# RFNODE.net
KiCad netlist of a schematic drawn in EAGLE
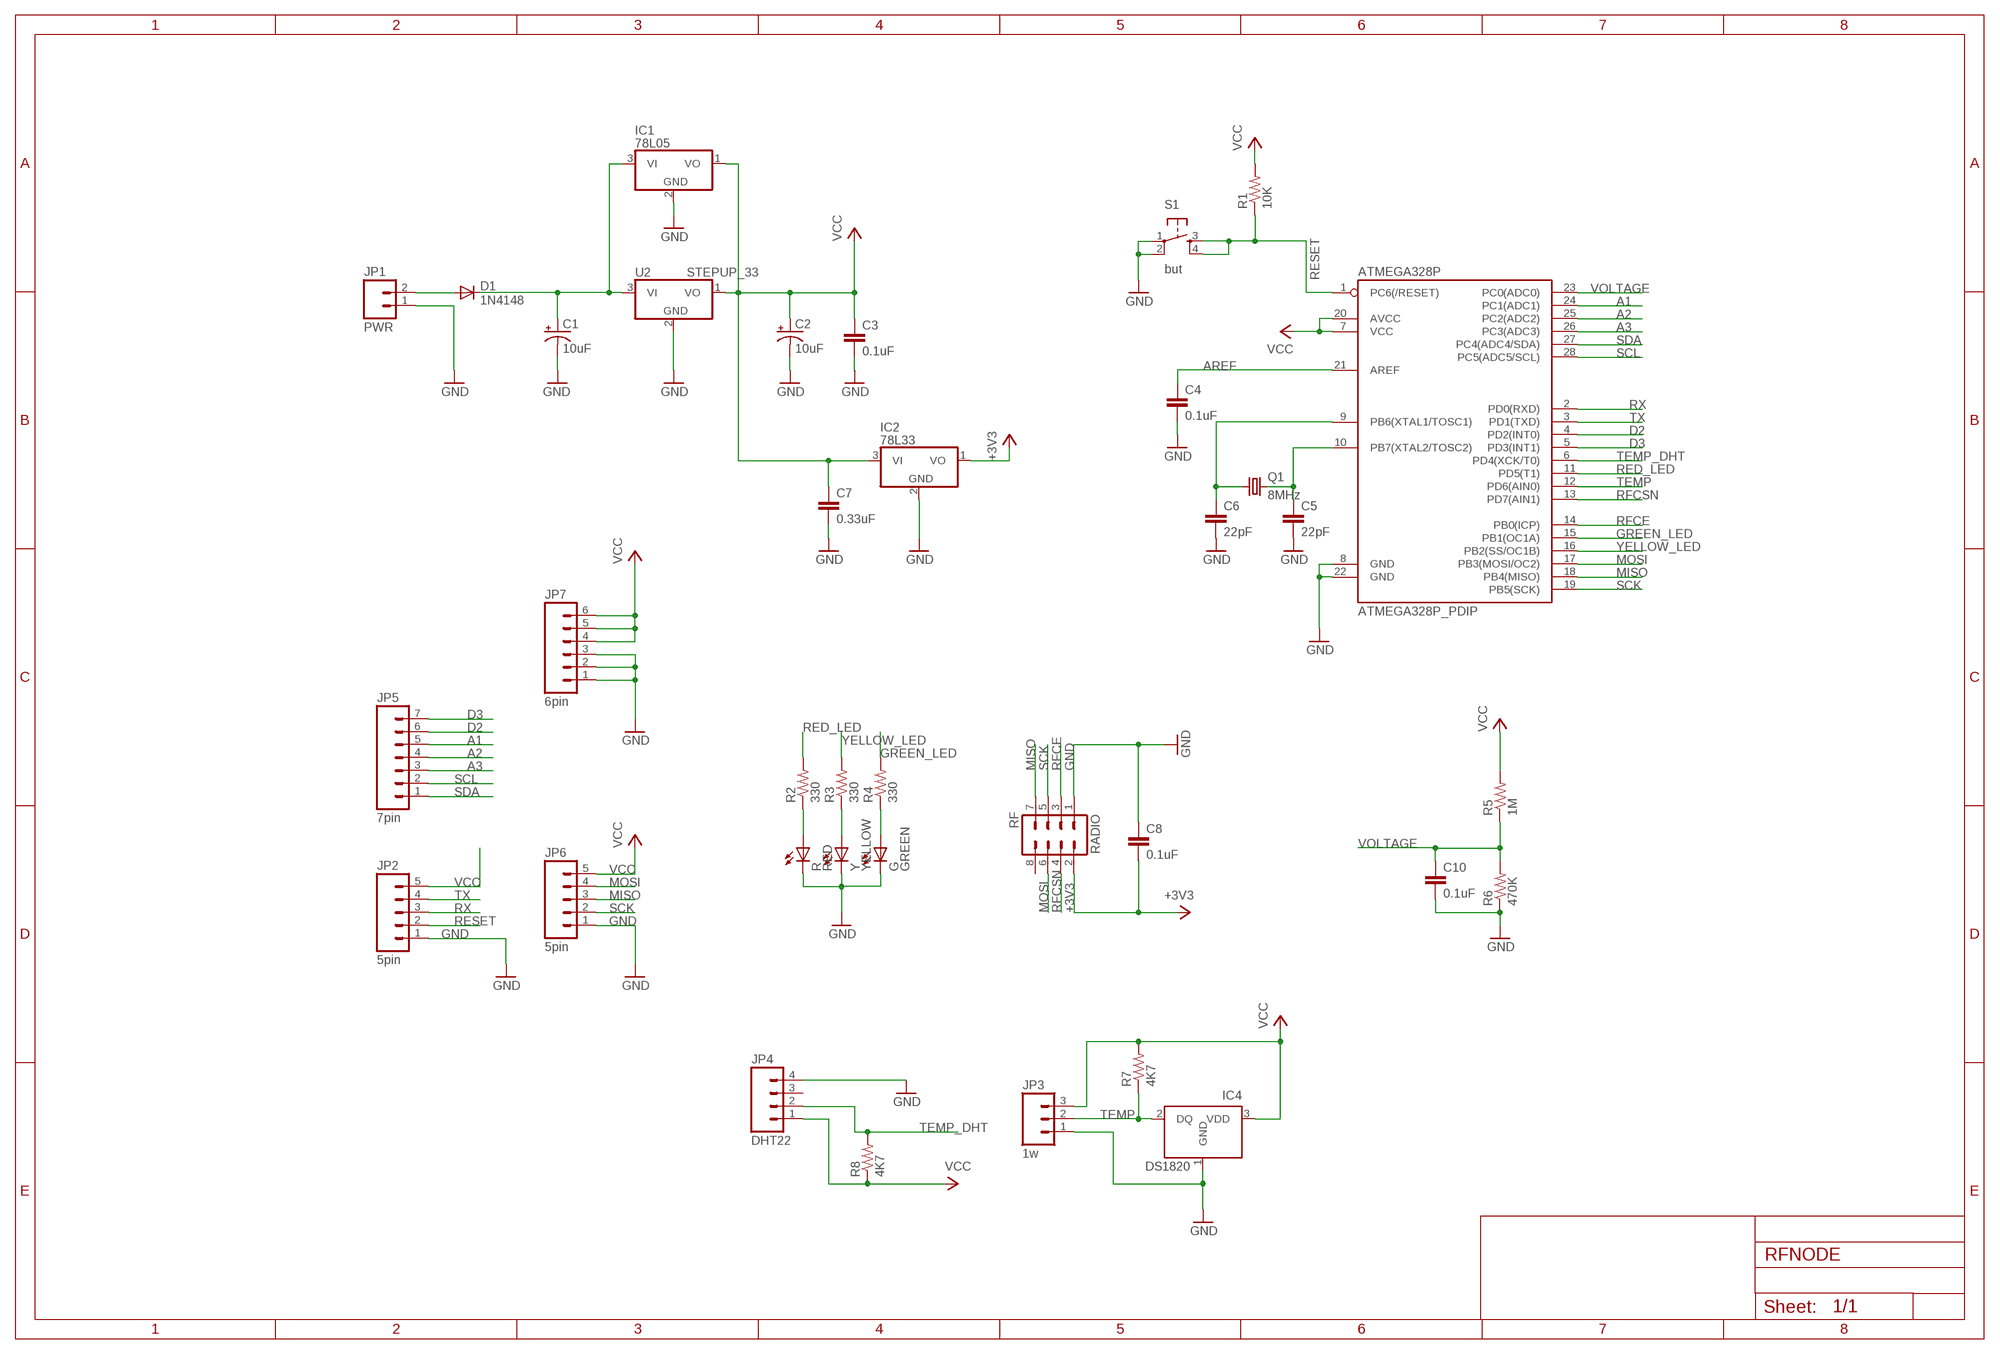
[diagram p0: schematic, sheet 1]

(export (version "E")
  (design (tool "Eeschema 10.0.6"))
  (components
    (comp (ref "ATMEGA328P")
      (value "ATMEGA328P_PDIP")
      (footprint "eagle-import:DIL28-3")
      (libsource (lib "eagle-import") (part "ATMEGA328P_PDIP"))
    )
    (comp (ref "C1")
      (value "10uF")
      (footprint "eagle-import:E2-4")
      (libsource (lib "eagle-import") (part "CPOL-USE2-4"))
    )
    (comp (ref "C2")
      (value "10uF")
      (footprint "eagle-import:E2-4")
      (libsource (lib "eagle-import") (part "CPOL-USE2-4"))
    )
    (comp (ref "C3")
      (value "0.1uF")
      (footprint "eagle-import:C1206")
      (libsource (lib "eagle-import") (part "C-EUC1206"))
    )
    (comp (ref "C4")
      (value "0.1uF")
      (footprint "eagle-import:C1206")
      (libsource (lib "eagle-import") (part "C-EUC1206"))
    )
    (comp (ref "C5")
      (value "22pF")
      (footprint "eagle-import:C1206")
      (libsource (lib "eagle-import") (part "C-EUC1206"))
    )
    (comp (ref "C6")
      (value "22pF")
      (footprint "eagle-import:C1206")
      (libsource (lib "eagle-import") (part "C-EUC1206"))
    )
    (comp (ref "C7")
      (value "0.33uF")
      (footprint "eagle-import:C1206")
      (libsource (lib "eagle-import") (part "C-EUC1206"))
    )
    (comp (ref "C8")
      (value "0.1uF")
      (footprint "eagle-import:C1206")
      (libsource (lib "eagle-import") (part "C-EUC1206"))
    )
    (comp (ref "C10")
      (value "0.1uF")
      (footprint "eagle-import:C1206")
      (libsource (lib "eagle-import") (part "C-EUC1206"))
    )
    (comp (ref "D1")
      (value "1N4148")
      (footprint "eagle-import:D-2.5")
      (libsource (lib "eagle-import") (part "DIODE-D-2.5"))
    )
    (comp (ref "G")
      (value "GREEN")
      (footprint "eagle-import:LED3MM")
      (libsource (lib "eagle-import") (part "LED3MM"))
    )
    (comp (ref "IC1")
      (value "78L05")
      (footprint "eagle-import:TO92")
      (libsource (lib "eagle-import") (part "78ZL05"))
    )
    (comp (ref "IC2")
      (value "78L33")
      (footprint "eagle-import:TO92")
      (libsource (lib "eagle-import") (part "78ZL05"))
    )
    (comp (ref "IC4")
      (value "DS1820")
      (footprint "eagle-import:TO-92")
      (libsource (lib "eagle-import") (part "DS1820"))
    )
    (comp (ref "JP1")
      (value "PWR")
      (footprint "eagle-import:MOLEX-1X2")
      (libsource (lib "eagle-import") (part "M02POLAR"))
    )
    (comp (ref "JP2")
      (value "5pin")
      (footprint "eagle-import:1X05")
      (libsource (lib "eagle-import") (part "M05PTH"))
    )
    (comp (ref "JP3")
      (value "1w")
      (footprint "eagle-import:1X03")
      (libsource (lib "eagle-import") (part "M03PTH"))
    )
    (comp (ref "JP4")
      (value "DHT22")
      (footprint "eagle-import:1X04")
      (libsource (lib "eagle-import") (part "M04PTH"))
    )
    (comp (ref "JP5")
      (value "7pin")
      (footprint "eagle-import:1X07")
      (libsource (lib "eagle-import") (part "M07"))
    )
    (comp (ref "JP6")
      (value "5pin")
      (footprint "eagle-import:1X05")
      (libsource (lib "eagle-import") (part "M05PTH"))
    )
    (comp (ref "JP7")
      (value "6pin")
      (footprint "eagle-import:1X06")
      (libsource (lib "eagle-import") (part "M06SIP"))
    )
    (comp (ref "Q1")
      (value "8MHz")
      (footprint "eagle-import:HC49_S")
      (libsource (lib "eagle-import") (part "CRYSTALHC49S"))
    )
    (comp (ref "R")
      (value "RED")
      (footprint "eagle-import:LED3MM")
      (libsource (lib "eagle-import") (part "LED3MM"))
    )
    (comp (ref "R1")
      (value "10K")
      (footprint "eagle-import:R1206")
      (libsource (lib "eagle-import") (part "R-US_R1206"))
    )
    (comp (ref "R2")
      (value "330")
      (footprint "eagle-import:R1206")
      (libsource (lib "eagle-import") (part "R-US_R1206"))
    )
    (comp (ref "R3")
      (value "330")
      (footprint "eagle-import:R1206")
      (libsource (lib "eagle-import") (part "R-US_R1206"))
    )
    (comp (ref "R4")
      (value "330")
      (footprint "eagle-import:R1206")
      (libsource (lib "eagle-import") (part "R-US_R1206"))
    )
    (comp (ref "R5")
      (value "1M")
      (footprint "eagle-import:R1206")
      (libsource (lib "eagle-import") (part "R-US_R1206"))
    )
    (comp (ref "R6")
      (value "470K")
      (footprint "eagle-import:R1206")
      (libsource (lib "eagle-import") (part "R-US_R1206"))
    )
    (comp (ref "R7")
      (value "4K7")
      (footprint "eagle-import:R1206")
      (libsource (lib "eagle-import") (part "R-US_R1206"))
    )
    (comp (ref "R8")
      (value "4K7")
      (footprint "eagle-import:R1206")
      (libsource (lib "eagle-import") (part "R-US_R1206"))
    )
    (comp (ref "RADIO")
      (value "RF")
      (footprint "eagle-import:2X4")
      (libsource (lib "eagle-import") (part "M04X2"))
    )
    (comp (ref "S1")
      (value "but")
      (footprint "eagle-import:TACTILE-PTH")
      (libsource (lib "eagle-import") (part "TAC_SWITCHPTH"))
    )
    (comp (ref "U2")
      (value "STEPUP_33")
      (footprint "eagle-import:1X03")
      (libsource (lib "eagle-import") (part "DC-DC_STEPUP"))
    )
    (comp (ref "Y")
      (value "YELLOW")
      (footprint "eagle-import:LED3MM")
      (libsource (lib "eagle-import") (part "LED3MM"))
    )
  )
  (nets
    (net (code "1") (name "+3V3") (class "Default")
      (node (ref "C8") (pin "2") (pinfunction "2_2") (pintype "passive"))
      (node (ref "IC2") (pin "1") (pinfunction "VO_1") (pintype "passive"))
      (node (ref "RADIO") (pin "2") (pinfunction "2_2") (pintype "passive"))
    )
    (net (code "2") (name "/A1") (class "Default")
      (node (ref "ATMEGA328P") (pin "24") (pinfunction "PC1(ADC1)_24") (pintype "bidirectional"))
      (node (ref "JP5") (pin "5") (pinfunction "5_5") (pintype "passive"))
    )
    (net (code "3") (name "/A2") (class "Default")
      (node (ref "ATMEGA328P") (pin "25") (pinfunction "PC2(ADC2)_25") (pintype "bidirectional"))
      (node (ref "JP5") (pin "4") (pinfunction "4_4") (pintype "passive"))
    )
    (net (code "4") (name "/A3") (class "Default")
      (node (ref "ATMEGA328P") (pin "26") (pinfunction "PC3(ADC3)_26") (pintype "bidirectional"))
      (node (ref "JP5") (pin "3") (pinfunction "3_3") (pintype "passive"))
    )
    (net (code "5") (name "/AREF") (class "Default")
      (node (ref "ATMEGA328P") (pin "21") (pinfunction "AREF_21") (pintype "bidirectional"))
      (node (ref "C4") (pin "1") (pinfunction "1_1") (pintype "passive"))
    )
    (net (code "6") (name "/D2") (class "Default")
      (node (ref "ATMEGA328P") (pin "4") (pinfunction "PD2(INT0)_4") (pintype "bidirectional"))
      (node (ref "JP5") (pin "6") (pinfunction "6_6") (pintype "passive"))
    )
    (net (code "7") (name "/D3") (class "Default")
      (node (ref "ATMEGA328P") (pin "5") (pinfunction "PD3(INT1)_5") (pintype "bidirectional"))
      (node (ref "JP5") (pin "7") (pinfunction "7_7") (pintype "passive"))
    )
    (net (code "8") (name "/GREEN_LED") (class "Default")
      (node (ref "ATMEGA328P") (pin "15") (pinfunction "PB1(OC1A)_15") (pintype "bidirectional"))
      (node (ref "R4") (pin "2") (pinfunction "2_2") (pintype "passive"))
    )
    (net (code "9") (name "/MISO") (class "Default")
      (node (ref "ATMEGA328P") (pin "18") (pinfunction "PB4(MISO)_18") (pintype "bidirectional"))
      (node (ref "JP6") (pin "4") (pinfunction "4_4") (pintype "passive"))
      (node (ref "RADIO") (pin "7") (pinfunction "7_7") (pintype "passive"))
    )
    (net (code "10") (name "/MOSI") (class "Default")
      (node (ref "ATMEGA328P") (pin "17") (pinfunction "PB3(MOSI/OC2)_17") (pintype "bidirectional"))
      (node (ref "JP6") (pin "3") (pinfunction "3_3") (pintype "passive"))
      (node (ref "RADIO") (pin "6") (pinfunction "6_6") (pintype "passive"))
    )
    (net (code "11") (name "/RED_LED") (class "Default")
      (node (ref "ATMEGA328P") (pin "11") (pinfunction "PD5(T1)_11") (pintype "bidirectional"))
      (node (ref "R2") (pin "2") (pinfunction "2_2") (pintype "passive"))
    )
    (net (code "12") (name "/RESET") (class "Default")
      (node (ref "ATMEGA328P") (pin "1") (pinfunction "PC6(/RESET)_1") (pintype "bidirectional"))
      (node (ref "JP2") (pin "2") (pinfunction "2_2") (pintype "passive"))
      (node (ref "R1") (pin "1") (pinfunction "1_1") (pintype "passive"))
      (node (ref "S1") (pin "3") (pinfunction "3_3") (pintype "passive"))
      (node (ref "S1") (pin "4") (pinfunction "4_4") (pintype "passive"))
    )
    (net (code "13") (name "/RFCE") (class "Default")
      (node (ref "ATMEGA328P") (pin "14") (pinfunction "PB0(ICP)_14") (pintype "bidirectional"))
      (node (ref "RADIO") (pin "3") (pinfunction "3_3") (pintype "passive"))
    )
    (net (code "14") (name "/RFCSN") (class "Default")
      (node (ref "ATMEGA328P") (pin "13") (pinfunction "PD7(AIN1)_13") (pintype "bidirectional"))
      (node (ref "RADIO") (pin "4") (pinfunction "4_4") (pintype "passive"))
    )
    (net (code "15") (name "/RX") (class "Default")
      (node (ref "ATMEGA328P") (pin "2") (pinfunction "PD0(RXD)_2") (pintype "bidirectional"))
      (node (ref "JP2") (pin "3") (pinfunction "3_3") (pintype "passive"))
    )
    (net (code "16") (name "/SCK") (class "Default")
      (node (ref "ATMEGA328P") (pin "19") (pinfunction "PB5(SCK)_19") (pintype "bidirectional"))
      (node (ref "JP6") (pin "2") (pinfunction "2_2") (pintype "passive"))
      (node (ref "RADIO") (pin "5") (pinfunction "5_5") (pintype "passive"))
    )
    (net (code "17") (name "/SCL") (class "Default")
      (node (ref "ATMEGA328P") (pin "28") (pinfunction "PC5(ADC5/SCL)_28") (pintype "bidirectional"))
      (node (ref "JP5") (pin "1") (pinfunction "1_1") (pintype "passive"))
    )
    (net (code "18") (name "/SDA") (class "Default")
      (node (ref "ATMEGA328P") (pin "27") (pinfunction "PC4(ADC4/SDA)_27") (pintype "bidirectional"))
      (node (ref "JP5") (pin "2") (pinfunction "2_2") (pintype "passive"))
    )
    (net (code "19") (name "/TEMP") (class "Default")
      (node (ref "ATMEGA328P") (pin "12") (pinfunction "PD6(AIN0)_12") (pintype "bidirectional"))
      (node (ref "IC4") (pin "2") (pinfunction "DQ_2") (pintype "output"))
      (node (ref "JP3") (pin "2") (pinfunction "2_2") (pintype "passive"))
      (node (ref "R7") (pin "1") (pinfunction "1_1") (pintype "passive"))
    )
    (net (code "20") (name "/TEMP_DHT") (class "Default")
      (node (ref "ATMEGA328P") (pin "6") (pinfunction "PD4(XCK/T0)_6") (pintype "bidirectional"))
      (node (ref "JP4") (pin "2") (pinfunction "2_2") (pintype "passive"))
      (node (ref "R8") (pin "2") (pinfunction "2_2") (pintype "passive"))
    )
    (net (code "21") (name "/TX") (class "Default")
      (node (ref "ATMEGA328P") (pin "3") (pinfunction "PD1(TXD)_3") (pintype "bidirectional"))
      (node (ref "JP2") (pin "4") (pinfunction "4_4") (pintype "passive"))
    )
    (net (code "22") (name "/VOLTAGE") (class "Default")
      (node (ref "ATMEGA328P") (pin "23") (pinfunction "PC0(ADC0)_23") (pintype "bidirectional"))
      (node (ref "C10") (pin "1") (pinfunction "1_1") (pintype "passive"))
      (node (ref "R5") (pin "1") (pinfunction "1_1") (pintype "passive"))
      (node (ref "R6") (pin "2") (pinfunction "2_2") (pintype "passive"))
    )
    (net (code "23") (name "/YELLOW_LED") (class "Default")
      (node (ref "ATMEGA328P") (pin "16") (pinfunction "PB2(SS/OC1B)_16") (pintype "bidirectional"))
      (node (ref "R3") (pin "2") (pinfunction "2_2") (pintype "passive"))
    )
    (net (code "24") (name "GND") (class "Default")
      (node (ref "ATMEGA328P") (pin "22") (pinfunction "GND_22") (pintype "bidirectional"))
      (node (ref "ATMEGA328P") (pin "8") (pinfunction "GND_8") (pintype "bidirectional"))
      (node (ref "C1") (pin "-") (pinfunction "-_-") (pintype "passive"))
      (node (ref "C10") (pin "2") (pinfunction "2_2") (pintype "passive"))
      (node (ref "C2") (pin "-") (pinfunction "-_-") (pintype "passive"))
      (node (ref "C3") (pin "2") (pinfunction "2_2") (pintype "passive"))
      (node (ref "C4") (pin "2") (pinfunction "2_2") (pintype "passive"))
      (node (ref "C5") (pin "2") (pinfunction "2_2") (pintype "passive"))
      (node (ref "C6") (pin "2") (pinfunction "2_2") (pintype "passive"))
      (node (ref "C7") (pin "2") (pinfunction "2_2") (pintype "passive"))
      (node (ref "C8") (pin "1") (pinfunction "1_1") (pintype "passive"))
      (node (ref "G") (pin "K") (pinfunction "C_K") (pintype "passive"))
      (node (ref "IC1") (pin "2") (pinfunction "GND_2") (pintype "passive"))
      (node (ref "IC2") (pin "2") (pinfunction "GND_2") (pintype "passive"))
      (node (ref "IC4") (pin "1") (pinfunction "GND_1") (pintype "power_in"))
      (node (ref "JP1") (pin "1") (pinfunction "1_1") (pintype "passive"))
      (node (ref "JP2") (pin "1") (pinfunction "1_1") (pintype "passive"))
      (node (ref "JP3") (pin "1") (pinfunction "1_1") (pintype "passive"))
      (node (ref "JP4") (pin "4") (pinfunction "4_4") (pintype "passive"))
      (node (ref "JP6") (pin "1") (pinfunction "1_1") (pintype "passive"))
      (node (ref "JP7") (pin "1") (pinfunction "1_1") (pintype "passive"))
      (node (ref "JP7") (pin "2") (pinfunction "2_2") (pintype "passive"))
      (node (ref "JP7") (pin "3") (pinfunction "3_3") (pintype "passive"))
      (node (ref "R") (pin "K") (pinfunction "C_K") (pintype "passive"))
      (node (ref "R6") (pin "1") (pinfunction "1_1") (pintype "passive"))
      (node (ref "RADIO") (pin "1") (pinfunction "1_1") (pintype "passive"))
      (node (ref "S1") (pin "1") (pinfunction "1_1") (pintype "passive"))
      (node (ref "S1") (pin "2") (pinfunction "2_2") (pintype "passive"))
      (node (ref "U2") (pin "2") (pinfunction "GND_2") (pintype "passive"))
      (node (ref "Y") (pin "K") (pinfunction "C_K") (pintype "passive"))
    )
    (net (code "25") (name "Net-(ATMEGA328P-PB6(XTAL1{slash}TOSC1))") (class "Default")
      (node (ref "ATMEGA328P") (pin "9") (pinfunction "PB6(XTAL1/TOSC1)_9") (pintype "bidirectional"))
      (node (ref "C6") (pin "1") (pinfunction "1_1") (pintype "passive"))
      (node (ref "Q1") (pin "1") (pinfunction "1_1") (pintype "passive"))
    )
    (net (code "26") (name "Net-(ATMEGA328P-PB7(XTAL2{slash}TOSC2))") (class "Default")
      (node (ref "ATMEGA328P") (pin "10") (pinfunction "PB7(XTAL2/TOSC2)_10") (pintype "bidirectional"))
      (node (ref "C5") (pin "1") (pinfunction "1_1") (pintype "passive"))
      (node (ref "Q1") (pin "2") (pinfunction "2_2") (pintype "passive"))
    )
    (net (code "27") (name "Net-(D1-PadA)") (class "Default")
      (node (ref "D1") (pin "A") (pinfunction "A_A") (pintype "passive"))
      (node (ref "JP1") (pin "2") (pinfunction "2_2") (pintype "passive"))
    )
    (net (code "28") (name "Net-(G-PadA)") (class "Default")
      (node (ref "G") (pin "A") (pinfunction "A_A") (pintype "passive"))
      (node (ref "R4") (pin "1") (pinfunction "1_1") (pintype "passive"))
    )
    (net (code "29") (name "Net-(IC1-VI)") (class "Default")
      (node (ref "C1") (pin "+") (pinfunction "+_+") (pintype "passive"))
      (node (ref "D1") (pin "C") (pinfunction "C_C") (pintype "passive"))
      (node (ref "IC1") (pin "3") (pinfunction "VI_3") (pintype "input"))
      (node (ref "U2") (pin "3") (pinfunction "VI_3") (pintype "input"))
    )
    (net (code "30") (name "Net-(R-PadA)") (class "Default")
      (node (ref "R") (pin "A") (pinfunction "A_A") (pintype "passive"))
      (node (ref "R2") (pin "1") (pinfunction "1_1") (pintype "passive"))
    )
    (net (code "31") (name "Net-(R3-Pad1)") (class "Default")
      (node (ref "R3") (pin "1") (pinfunction "1_1") (pintype "passive"))
      (node (ref "Y") (pin "A") (pinfunction "A_A") (pintype "passive"))
    )
    (net (code "32") (name "VCC") (class "Default")
      (node (ref "ATMEGA328P") (pin "20") (pinfunction "AVCC_20") (pintype "bidirectional"))
      (node (ref "ATMEGA328P") (pin "7") (pinfunction "VCC_7") (pintype "bidirectional"))
      (node (ref "C2") (pin "+") (pinfunction "+_+") (pintype "passive"))
      (node (ref "C3") (pin "1") (pinfunction "1_1") (pintype "passive"))
      (node (ref "C7") (pin "1") (pinfunction "1_1") (pintype "passive"))
      (node (ref "IC1") (pin "1") (pinfunction "VO_1") (pintype "passive"))
      (node (ref "IC2") (pin "3") (pinfunction "VI_3") (pintype "input"))
      (node (ref "IC4") (pin "3") (pinfunction "VDD_3") (pintype "input"))
      (node (ref "JP2") (pin "5") (pinfunction "5_5") (pintype "passive"))
      (node (ref "JP3") (pin "3") (pinfunction "3_3") (pintype "passive"))
      (node (ref "JP4") (pin "1") (pinfunction "1_1") (pintype "passive"))
      (node (ref "JP6") (pin "5") (pinfunction "5_5") (pintype "passive"))
      (node (ref "JP7") (pin "4") (pinfunction "4_4") (pintype "passive"))
      (node (ref "JP7") (pin "5") (pinfunction "5_5") (pintype "passive"))
      (node (ref "JP7") (pin "6") (pinfunction "6_6") (pintype "passive"))
      (node (ref "R1") (pin "2") (pinfunction "2_2") (pintype "passive"))
      (node (ref "R5") (pin "2") (pinfunction "2_2") (pintype "passive"))
      (node (ref "R7") (pin "2") (pinfunction "2_2") (pintype "passive"))
      (node (ref "R8") (pin "1") (pinfunction "1_1") (pintype "passive"))
      (node (ref "U2") (pin "1") (pinfunction "VO_1") (pintype "passive"))
    )
    (net (code "33") (name "unconnected-(JP4-Pad3)") (class "Default")
      (node (ref "JP4") (pin "3") (pinfunction "3_3") (pintype "passive"))
    )
    (net (code "34") (name "unconnected-(RADIO-Pad8)") (class "Default")
      (node (ref "RADIO") (pin "8") (pinfunction "8_8") (pintype "passive"))
    )
  )
)
